# driver_ckt_4_bjtTH.net
KiCad netlist of a schematic drawn in EAGLE
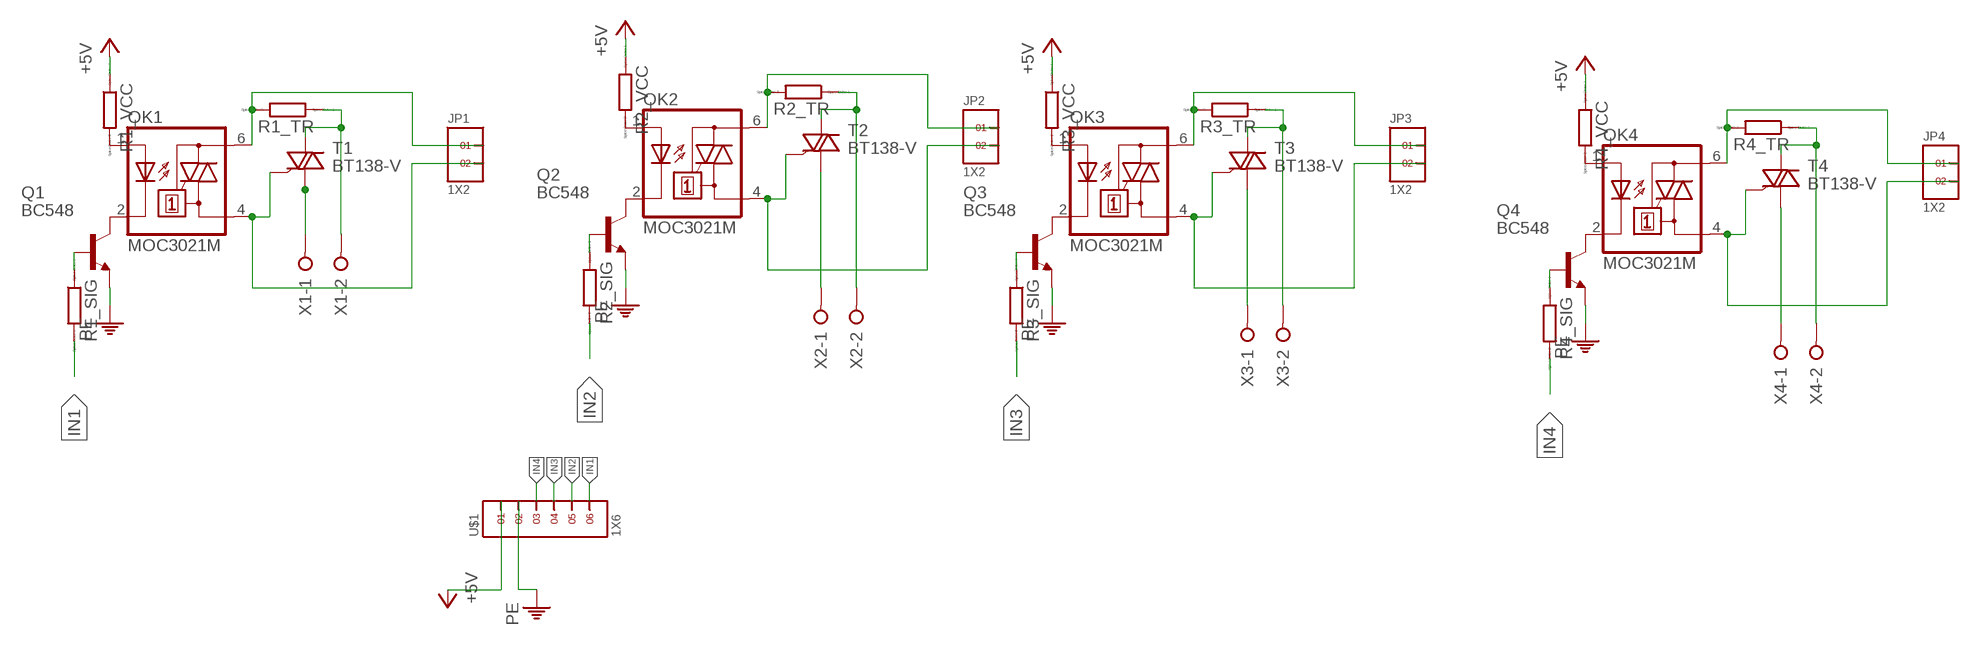
[diagram p0: schematic, sheet 1]

(export (version "E")
  (design (tool "Eeschema 10.0.6"))
  (components
    (comp (ref "JP1")
      (value "1X2")
      (footprint "eagle-import:1X2")
      (libsource (lib "eagle-import") (part "1X2"))
    )
    (comp (ref "JP2")
      (value "1X2")
      (footprint "eagle-import:1X2")
      (libsource (lib "eagle-import") (part "1X2"))
    )
    (comp (ref "JP3")
      (value "1X2")
      (footprint "eagle-import:1X2")
      (libsource (lib "eagle-import") (part "1X2"))
    )
    (comp (ref "JP4")
      (value "1X2")
      (footprint "eagle-import:1X2")
      (libsource (lib "eagle-import") (part "1X2"))
    )
    (comp (ref "OK1")
      (value "MOC3021M")
      (footprint "eagle-import:DIL06")
      (fields (field (name "MF") "FAIRCHILD SEMICONDUCTOR") (field (name "MPN") "MOC3021-M"))
      (libsource (lib "eagle-import") (part "MOC30M21"))
    )
    (comp (ref "OK2")
      (value "MOC3021M")
      (footprint "eagle-import:DIL06")
      (fields (field (name "MF") "FAIRCHILD SEMICONDUCTOR") (field (name "MPN") "MOC3021-M"))
      (libsource (lib "eagle-import") (part "MOC30M21"))
    )
    (comp (ref "OK3")
      (value "MOC3021M")
      (footprint "eagle-import:DIL06")
      (fields (field (name "MF") "FAIRCHILD SEMICONDUCTOR") (field (name "MPN") "MOC3021-M"))
      (libsource (lib "eagle-import") (part "MOC30M21"))
    )
    (comp (ref "OK4")
      (value "MOC3021M")
      (footprint "eagle-import:DIL06")
      (fields (field (name "MF") "FAIRCHILD SEMICONDUCTOR") (field (name "MPN") "MOC3021-M"))
      (libsource (lib "eagle-import") (part "MOC30M21"))
    )
    (comp (ref "Q1")
      (value "BC548")
      (footprint "eagle-import:TO92-EBC")
      (libsource (lib "eagle-import") (part "BC548"))
    )
    (comp (ref "Q2")
      (value "BC548")
      (footprint "eagle-import:TO92-EBC")
      (libsource (lib "eagle-import") (part "BC548"))
    )
    (comp (ref "Q3")
      (value "BC548")
      (footprint "eagle-import:TO92-EBC")
      (libsource (lib "eagle-import") (part "BC548"))
    )
    (comp (ref "Q4")
      (value "BC548")
      (footprint "eagle-import:TO92-EBC")
      (libsource (lib "eagle-import") (part "BC548"))
    )
    (comp (ref "R1_SIG")
      (value "RR1206")
      (footprint "eagle-import:R1206")
      (libsource (lib "eagle-import") (part "RR1206"))
    )
    (comp (ref "R1_TR")
      (value "RR1206")
      (footprint "eagle-import:R1206")
      (libsource (lib "eagle-import") (part "RR1206"))
    )
    (comp (ref "R1_VCC")
      (value "RR1206")
      (footprint "eagle-import:R1206")
      (libsource (lib "eagle-import") (part "RR1206"))
    )
    (comp (ref "R2_SIG")
      (value "RR1206")
      (footprint "eagle-import:R1206")
      (libsource (lib "eagle-import") (part "RR1206"))
    )
    (comp (ref "R2_TR")
      (value "RR1206")
      (footprint "eagle-import:R1206")
      (libsource (lib "eagle-import") (part "RR1206"))
    )
    (comp (ref "R2_VCC")
      (value "RR1206")
      (footprint "eagle-import:R1206")
      (libsource (lib "eagle-import") (part "RR1206"))
    )
    (comp (ref "R3_SIG")
      (value "RR1206")
      (footprint "eagle-import:R1206")
      (libsource (lib "eagle-import") (part "RR1206"))
    )
    (comp (ref "R3_TR")
      (value "RR1206")
      (footprint "eagle-import:R1206")
      (libsource (lib "eagle-import") (part "RR1206"))
    )
    (comp (ref "R3_VCC")
      (value "RR1206")
      (footprint "eagle-import:R1206")
      (libsource (lib "eagle-import") (part "RR1206"))
    )
    (comp (ref "R4_SIG")
      (value "RR1206")
      (footprint "eagle-import:R1206")
      (libsource (lib "eagle-import") (part "RR1206"))
    )
    (comp (ref "R4_TR")
      (value "RR1206")
      (footprint "eagle-import:R1206")
      (libsource (lib "eagle-import") (part "RR1206"))
    )
    (comp (ref "R4_VCC")
      (value "RR1206")
      (footprint "eagle-import:R1206")
      (libsource (lib "eagle-import") (part "RR1206"))
    )
    (comp (ref "T1")
      (value "BT138-V")
      (footprint "eagle-import:TO220BV")
      (libsource (lib "eagle-import") (part "BT138-V"))
    )
    (comp (ref "T2")
      (value "BT138-V")
      (footprint "eagle-import:TO220BV")
      (libsource (lib "eagle-import") (part "BT138-V"))
    )
    (comp (ref "T3")
      (value "BT138-V")
      (footprint "eagle-import:TO220BV")
      (libsource (lib "eagle-import") (part "BT138-V"))
    )
    (comp (ref "T4")
      (value "BT138-V")
      (footprint "eagle-import:TO220BV")
      (libsource (lib "eagle-import") (part "BT138-V"))
    )
    (comp (ref "U$1")
      (value "1X6")
      (footprint "eagle-import:1X6")
      (libsource (lib "eagle-import") (part "1X6"))
    )
    (comp (ref "X1")
      (value "W237-02P")
      (footprint "eagle-import:W237-132")
      (libsource (lib "eagle-import") (part "W237-02P"))
    )
    (comp (ref "X2")
      (value "W237-02P")
      (footprint "eagle-import:W237-132")
      (libsource (lib "eagle-import") (part "W237-02P"))
    )
    (comp (ref "X3")
      (value "W237-02P")
      (footprint "eagle-import:W237-132")
      (libsource (lib "eagle-import") (part "W237-02P"))
    )
    (comp (ref "X4")
      (value "W237-02P")
      (footprint "eagle-import:W237-132")
      (libsource (lib "eagle-import") (part "W237-02P"))
    )
  )
  (nets
    (net (code "1") (name "+5V") (class "Default")
      (node (ref "R1_VCC") (pin "1") (pinfunction "1_1") (pintype "passive"))
      (node (ref "R2_VCC") (pin "1") (pinfunction "1_1") (pintype "passive"))
      (node (ref "R3_VCC") (pin "1") (pinfunction "1_1") (pintype "passive"))
      (node (ref "R4_VCC") (pin "1") (pinfunction "1_1") (pintype "passive"))
      (node (ref "U$1") (pin "1") (pinfunction "1_1") (pintype "bidirectional"))
    )
    (net (code "2") (name "IN1") (class "Default")
      (node (ref "R1_SIG") (pin "2") (pinfunction "2_2") (pintype "passive"))
      (node (ref "U$1") (pin "6") (pinfunction "6_6") (pintype "bidirectional"))
    )
    (net (code "3") (name "IN2") (class "Default")
      (node (ref "R2_SIG") (pin "2") (pinfunction "2_2") (pintype "passive"))
      (node (ref "U$1") (pin "5") (pinfunction "5_5") (pintype "bidirectional"))
    )
    (net (code "4") (name "IN3") (class "Default")
      (node (ref "R3_SIG") (pin "2") (pinfunction "2_2") (pintype "passive"))
      (node (ref "U$1") (pin "4") (pinfunction "4_4") (pintype "bidirectional"))
    )
    (net (code "5") (name "IN4") (class "Default")
      (node (ref "R4_SIG") (pin "2") (pinfunction "2_2") (pintype "passive"))
      (node (ref "U$1") (pin "3") (pinfunction "3_3") (pintype "bidirectional"))
    )
    (net (code "6") (name "Net-(OK1-A)") (class "Default")
      (node (ref "OK1") (pin "1") (pinfunction "A_1") (pintype "passive"))
      (node (ref "R1_VCC") (pin "2") (pinfunction "2_2") (pintype "passive"))
    )
    (net (code "7") (name "Net-(OK1-A1)") (class "Default")
      (node (ref "JP1") (pin "2") (pinfunction "2_2") (pintype "bidirectional"))
      (node (ref "OK1") (pin "4") (pinfunction "A1_4") (pintype "passive"))
      (node (ref "T1") (pin "G") (pinfunction "G_G") (pintype "passive"))
    )
    (net (code "8") (name "Net-(OK1-A2)") (class "Default")
      (node (ref "JP1") (pin "1") (pinfunction "1_1") (pintype "bidirectional"))
      (node (ref "OK1") (pin "6") (pinfunction "A2_6") (pintype "passive"))
      (node (ref "R1_TR") (pin "2") (pinfunction "2_2") (pintype "passive"))
    )
    (net (code "9") (name "Net-(OK1-C)") (class "Default")
      (node (ref "OK1") (pin "2") (pinfunction "C_2") (pintype "passive"))
      (node (ref "Q1") (pin "C") (pinfunction "C_C") (pintype "passive"))
    )
    (net (code "10") (name "Net-(OK2-A)") (class "Default")
      (node (ref "OK2") (pin "1") (pinfunction "A_1") (pintype "passive"))
      (node (ref "R2_VCC") (pin "2") (pinfunction "2_2") (pintype "passive"))
    )
    (net (code "11") (name "Net-(OK2-A1)") (class "Default")
      (node (ref "JP2") (pin "2") (pinfunction "2_2") (pintype "bidirectional"))
      (node (ref "OK2") (pin "4") (pinfunction "A1_4") (pintype "passive"))
      (node (ref "T2") (pin "G") (pinfunction "G_G") (pintype "passive"))
    )
    (net (code "12") (name "Net-(OK2-A2)") (class "Default")
      (node (ref "JP2") (pin "1") (pinfunction "1_1") (pintype "bidirectional"))
      (node (ref "OK2") (pin "6") (pinfunction "A2_6") (pintype "passive"))
      (node (ref "R2_TR") (pin "2") (pinfunction "2_2") (pintype "passive"))
    )
    (net (code "13") (name "Net-(OK2-C)") (class "Default")
      (node (ref "OK2") (pin "2") (pinfunction "C_2") (pintype "passive"))
      (node (ref "Q2") (pin "C") (pinfunction "C_C") (pintype "passive"))
    )
    (net (code "14") (name "Net-(OK3-A)") (class "Default")
      (node (ref "OK3") (pin "1") (pinfunction "A_1") (pintype "passive"))
      (node (ref "R3_VCC") (pin "2") (pinfunction "2_2") (pintype "passive"))
    )
    (net (code "15") (name "Net-(OK3-A1)") (class "Default")
      (node (ref "JP3") (pin "2") (pinfunction "2_2") (pintype "bidirectional"))
      (node (ref "OK3") (pin "4") (pinfunction "A1_4") (pintype "passive"))
      (node (ref "T3") (pin "G") (pinfunction "G_G") (pintype "passive"))
    )
    (net (code "16") (name "Net-(OK3-A2)") (class "Default")
      (node (ref "JP3") (pin "1") (pinfunction "1_1") (pintype "bidirectional"))
      (node (ref "OK3") (pin "6") (pinfunction "A2_6") (pintype "passive"))
      (node (ref "R3_TR") (pin "2") (pinfunction "2_2") (pintype "passive"))
    )
    (net (code "17") (name "Net-(OK3-C)") (class "Default")
      (node (ref "OK3") (pin "2") (pinfunction "C_2") (pintype "passive"))
      (node (ref "Q3") (pin "C") (pinfunction "C_C") (pintype "passive"))
    )
    (net (code "18") (name "Net-(OK4-A)") (class "Default")
      (node (ref "OK4") (pin "1") (pinfunction "A_1") (pintype "passive"))
      (node (ref "R4_VCC") (pin "2") (pinfunction "2_2") (pintype "passive"))
    )
    (net (code "19") (name "Net-(OK4-A1)") (class "Default")
      (node (ref "JP4") (pin "2") (pinfunction "2_2") (pintype "bidirectional"))
      (node (ref "OK4") (pin "4") (pinfunction "A1_4") (pintype "passive"))
      (node (ref "T4") (pin "G") (pinfunction "G_G") (pintype "passive"))
    )
    (net (code "20") (name "Net-(OK4-A2)") (class "Default")
      (node (ref "JP4") (pin "1") (pinfunction "1_1") (pintype "bidirectional"))
      (node (ref "OK4") (pin "6") (pinfunction "A2_6") (pintype "passive"))
      (node (ref "R4_TR") (pin "2") (pinfunction "2_2") (pintype "passive"))
    )
    (net (code "21") (name "Net-(OK4-C)") (class "Default")
      (node (ref "OK4") (pin "2") (pinfunction "C_2") (pintype "passive"))
      (node (ref "Q4") (pin "C") (pinfunction "C_C") (pintype "passive"))
    )
    (net (code "22") (name "Net-(Q1-PadB)") (class "Default")
      (node (ref "Q1") (pin "B") (pinfunction "B_B") (pintype "passive"))
      (node (ref "R1_SIG") (pin "1") (pinfunction "1_1") (pintype "passive"))
    )
    (net (code "23") (name "Net-(Q2-PadB)") (class "Default")
      (node (ref "Q2") (pin "B") (pinfunction "B_B") (pintype "passive"))
      (node (ref "R2_SIG") (pin "1") (pinfunction "1_1") (pintype "passive"))
    )
    (net (code "24") (name "Net-(Q3-PadB)") (class "Default")
      (node (ref "Q3") (pin "B") (pinfunction "B_B") (pintype "passive"))
      (node (ref "R3_SIG") (pin "1") (pinfunction "1_1") (pintype "passive"))
    )
    (net (code "25") (name "Net-(Q4-PadB)") (class "Default")
      (node (ref "Q4") (pin "B") (pinfunction "B_B") (pintype "passive"))
      (node (ref "R4_SIG") (pin "1") (pinfunction "1_1") (pintype "passive"))
    )
    (net (code "26") (name "Net-(T1-A1)") (class "Default")
      (node (ref "T1") (pin "T1") (pinfunction "A1_T1") (pintype "passive"))
      (node (ref "X1") (pin "1") (pinfunction "KL_1") (pintype "passive"))
    )
    (net (code "27") (name "Net-(T1-A2)") (class "Default")
      (node (ref "R1_TR") (pin "1") (pinfunction "1_1") (pintype "passive"))
      (node (ref "T1") (pin "T2") (pinfunction "A2_T2") (pintype "passive"))
      (node (ref "X1") (pin "2") (pinfunction "KL_2") (pintype "passive"))
    )
    (net (code "28") (name "Net-(T2-A1)") (class "Default")
      (node (ref "T2") (pin "T1") (pinfunction "A1_T1") (pintype "passive"))
      (node (ref "X2") (pin "1") (pinfunction "KL_1") (pintype "passive"))
    )
    (net (code "29") (name "Net-(T2-A2)") (class "Default")
      (node (ref "R2_TR") (pin "1") (pinfunction "1_1") (pintype "passive"))
      (node (ref "T2") (pin "T2") (pinfunction "A2_T2") (pintype "passive"))
      (node (ref "X2") (pin "2") (pinfunction "KL_2") (pintype "passive"))
    )
    (net (code "30") (name "Net-(T3-A1)") (class "Default")
      (node (ref "T3") (pin "T1") (pinfunction "A1_T1") (pintype "passive"))
      (node (ref "X3") (pin "1") (pinfunction "KL_1") (pintype "passive"))
    )
    (net (code "31") (name "Net-(T3-A2)") (class "Default")
      (node (ref "R3_TR") (pin "1") (pinfunction "1_1") (pintype "passive"))
      (node (ref "T3") (pin "T2") (pinfunction "A2_T2") (pintype "passive"))
      (node (ref "X3") (pin "2") (pinfunction "KL_2") (pintype "passive"))
    )
    (net (code "32") (name "Net-(T4-A1)") (class "Default")
      (node (ref "T4") (pin "T1") (pinfunction "A1_T1") (pintype "passive"))
      (node (ref "X4") (pin "1") (pinfunction "KL_1") (pintype "passive"))
    )
    (net (code "33") (name "Net-(T4-A2)") (class "Default")
      (node (ref "R4_TR") (pin "1") (pinfunction "1_1") (pintype "passive"))
      (node (ref "T4") (pin "T2") (pinfunction "A2_T2") (pintype "passive"))
      (node (ref "X4") (pin "2") (pinfunction "KL_2") (pintype "passive"))
    )
    (net (code "34") (name "PE") (class "Default")
      (node (ref "Q1") (pin "E") (pinfunction "E_E") (pintype "passive"))
      (node (ref "Q2") (pin "E") (pinfunction "E_E") (pintype "passive"))
      (node (ref "Q3") (pin "E") (pinfunction "E_E") (pintype "passive"))
      (node (ref "Q4") (pin "E") (pinfunction "E_E") (pintype "passive"))
      (node (ref "U$1") (pin "2") (pinfunction "2_2") (pintype "bidirectional"))
    )
  )
)
